# 01_MCU.net
KiCad netlist of a schematic drawn in Altium Designer
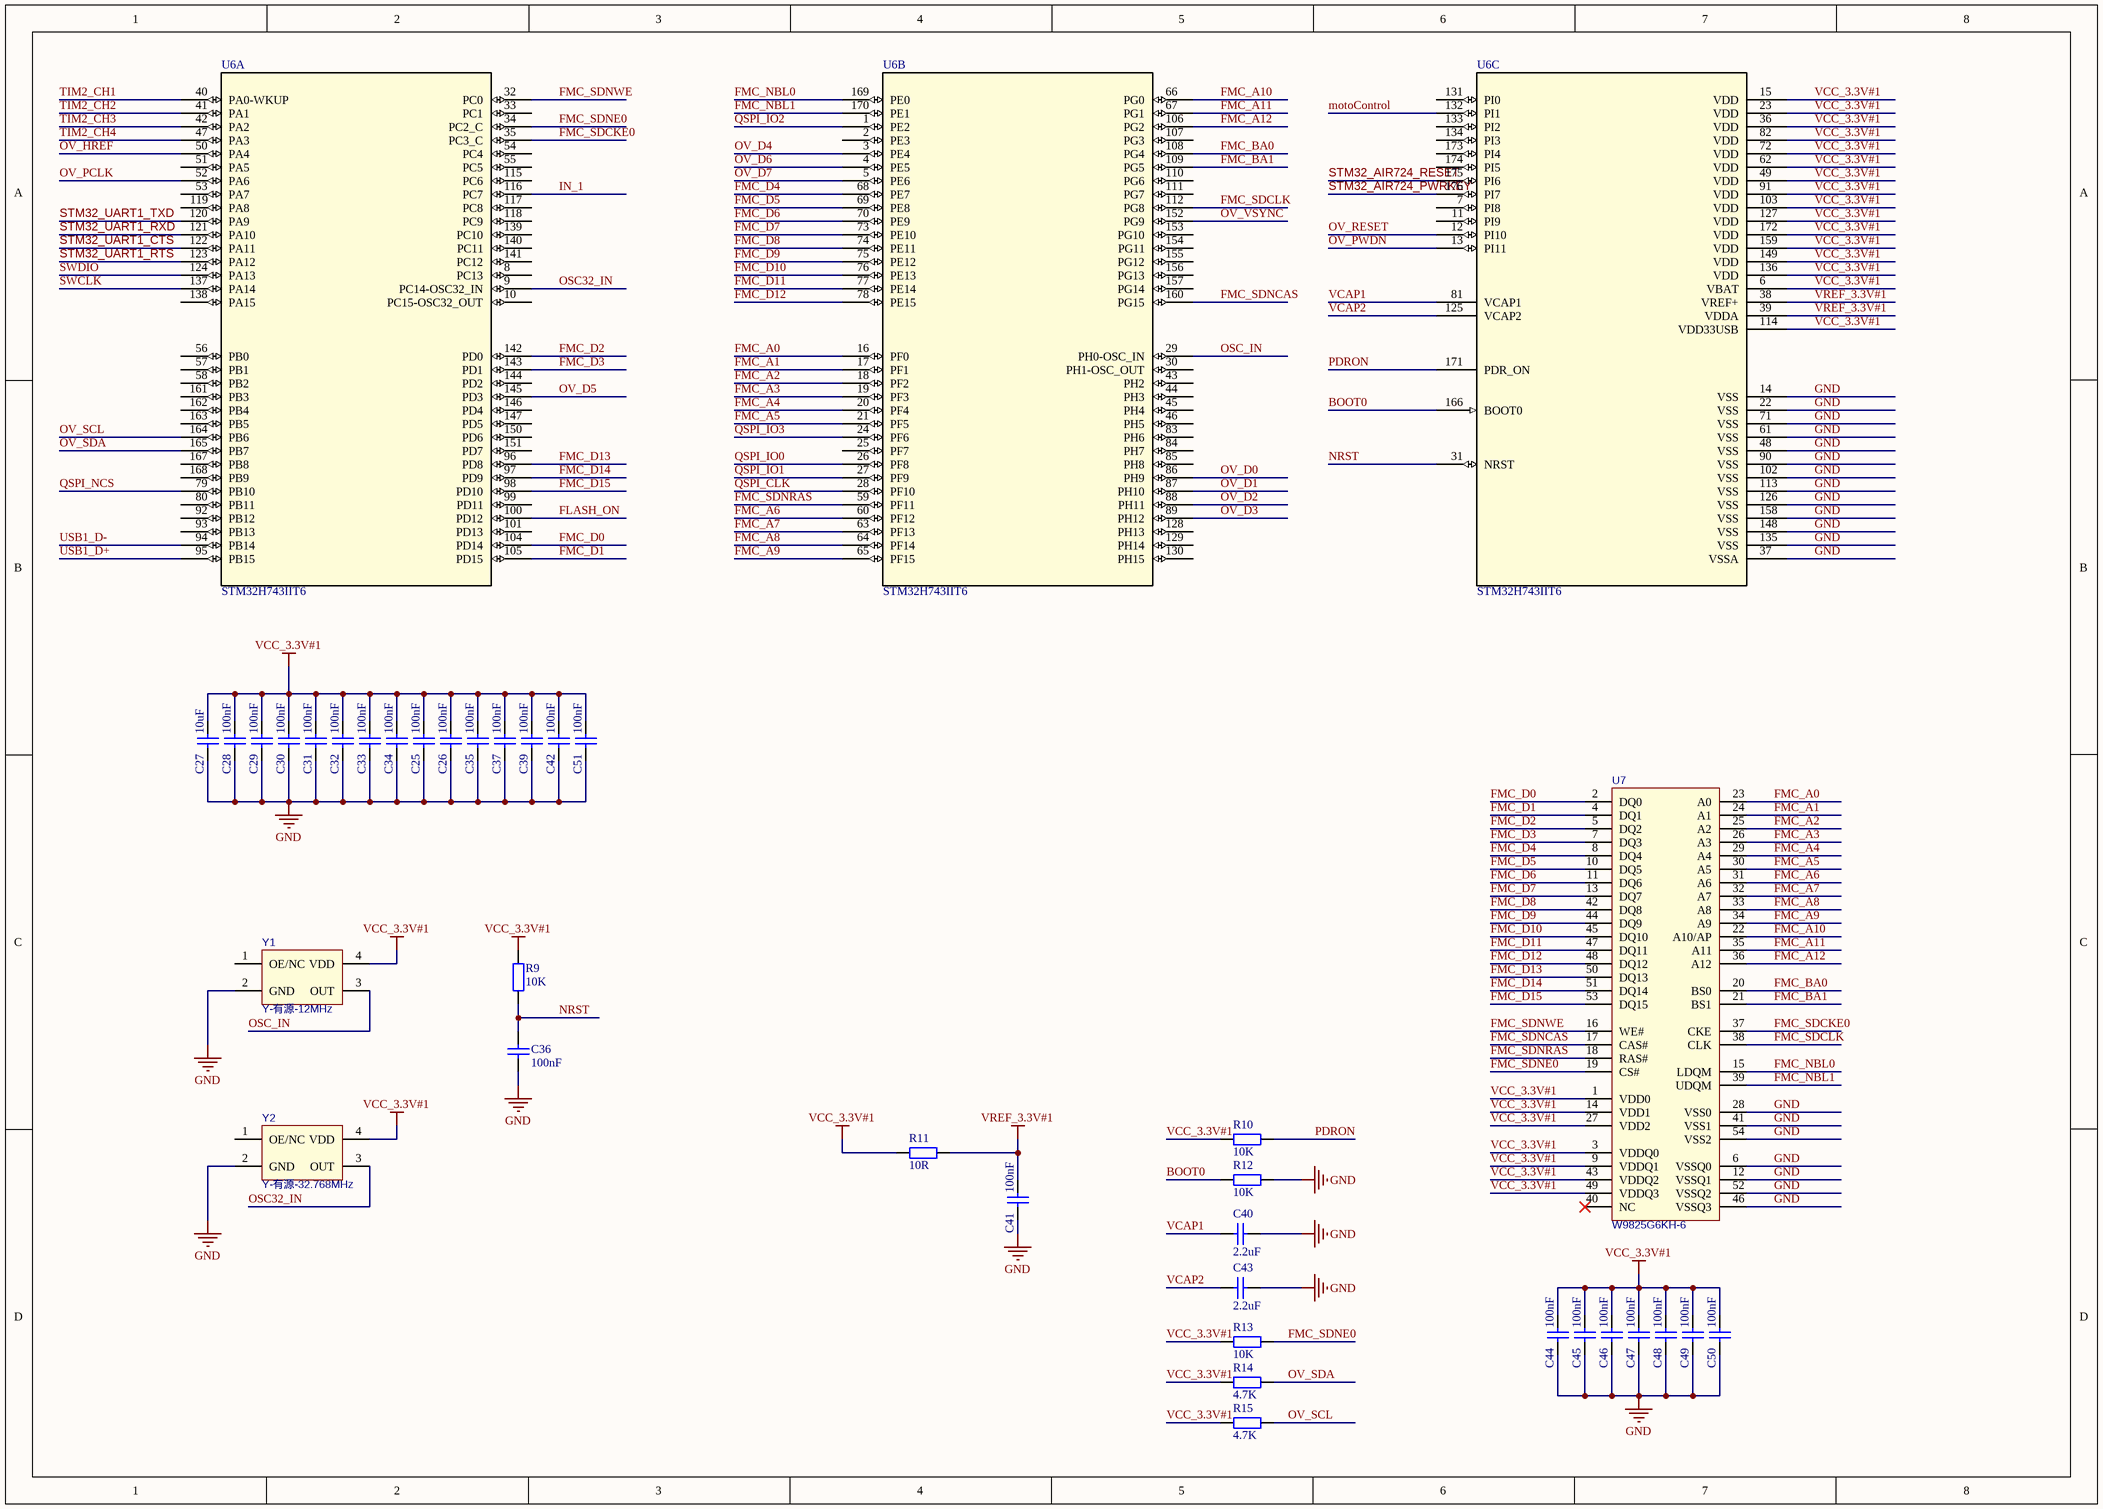
[diagram p0: 01_MCU.SchDoc]

(export (version "E")
  (design (tool "Eeschema 10.0.6"))
  (components
    (comp (ref "C25")
      (value "100nF")
      (footprint "0603-C")
      (description "贴片电容")
      (libsource (lib "封装库") (part "C"))
    )
    (comp (ref "C26")
      (value "100nF")
      (footprint "0603-C")
      (description "贴片电容")
      (libsource (lib "封装库") (part "C"))
    )
    (comp (ref "C27")
      (value "10uF")
      (footprint "0603-C")
      (description "贴片电容")
      (libsource (lib "封装库") (part "C"))
    )
    (comp (ref "C28")
      (value "100nF")
      (footprint "0603-C")
      (description "贴片电容")
      (libsource (lib "封装库") (part "C"))
    )
    (comp (ref "C29")
      (value "100nF")
      (footprint "0603-C")
      (description "贴片电容")
      (libsource (lib "封装库") (part "C"))
    )
    (comp (ref "C30")
      (value "100nF")
      (footprint "0603-C")
      (description "贴片电容")
      (libsource (lib "封装库") (part "C"))
    )
    (comp (ref "C31")
      (value "100nF")
      (footprint "0603-C")
      (description "贴片电容")
      (libsource (lib "封装库") (part "C"))
    )
    (comp (ref "C32")
      (value "100nF")
      (footprint "0603-C")
      (description "贴片电容")
      (libsource (lib "封装库") (part "C"))
    )
    (comp (ref "C33")
      (value "100nF")
      (footprint "0603-C")
      (description "贴片电容")
      (libsource (lib "封装库") (part "C"))
    )
    (comp (ref "C34")
      (value "100nF")
      (footprint "0603-C")
      (description "贴片电容")
      (libsource (lib "封装库") (part "C"))
    )
    (comp (ref "C35")
      (value "100nF")
      (footprint "0603-C")
      (description "贴片电容")
      (libsource (lib "封装库") (part "C"))
    )
    (comp (ref "C36")
      (value "100nF")
      (footprint "0603-C")
      (description "贴片电容")
      (libsource (lib "封装库") (part "C"))
    )
    (comp (ref "C37")
      (value "100nF")
      (footprint "0603-C")
      (description "贴片电容")
      (libsource (lib "封装库") (part "C"))
    )
    (comp (ref "C39")
      (value "100nF")
      (footprint "0603-C")
      (description "贴片电容")
      (libsource (lib "封装库") (part "C"))
    )
    (comp (ref "C40")
      (value "2.2uF")
      (footprint "0603-C")
      (description "贴片电容")
      (libsource (lib "封装库") (part "C"))
    )
    (comp (ref "C41")
      (value "100nF")
      (footprint "0603-C")
      (description "贴片电容")
      (libsource (lib "封装库") (part "C"))
    )
    (comp (ref "C42")
      (value "100nF")
      (footprint "0603-C")
      (description "贴片电容")
      (libsource (lib "封装库") (part "C"))
    )
    (comp (ref "C43")
      (value "2.2uF")
      (footprint "0603-C")
      (description "贴片电容")
      (libsource (lib "封装库") (part "C"))
    )
    (comp (ref "C44")
      (value "100nF")
      (footprint "0603-C")
      (description "贴片电容")
      (libsource (lib "封装库") (part "C"))
    )
    (comp (ref "C45")
      (value "100nF")
      (footprint "0603-C")
      (description "贴片电容")
      (libsource (lib "封装库") (part "C"))
    )
    (comp (ref "C46")
      (value "100nF")
      (footprint "0603-C")
      (description "贴片电容")
      (libsource (lib "封装库") (part "C"))
    )
    (comp (ref "C47")
      (value "100nF")
      (footprint "0603-C")
      (description "贴片电容")
      (libsource (lib "封装库") (part "C"))
    )
    (comp (ref "C48")
      (value "100nF")
      (footprint "0603-C")
      (description "贴片电容")
      (libsource (lib "封装库") (part "C"))
    )
    (comp (ref "C49")
      (value "100nF")
      (footprint "0603-C")
      (description "贴片电容")
      (libsource (lib "封装库") (part "C"))
    )
    (comp (ref "C50")
      (value "100nF")
      (footprint "0603-C")
      (description "贴片电容")
      (libsource (lib "封装库") (part "C"))
    )
    (comp (ref "C51")
      (value "100nF")
      (footprint "0603-C")
      (description "贴片电容")
      (libsource (lib "封装库") (part "C"))
    )
    (comp (ref "R9")
      (value "10K")
      (footprint "0603-R")
      (description "贴片电阻")
      (libsource (lib "封装库") (part "R"))
    )
    (comp (ref "R10")
      (value "10K")
      (footprint "0603-R")
      (description "贴片电阻")
      (libsource (lib "封装库") (part "R"))
    )
    (comp (ref "R11")
      (value "10R")
      (footprint "0603-R")
      (description "贴片电阻")
      (libsource (lib "封装库") (part "R"))
    )
    (comp (ref "R12")
      (value "10K")
      (footprint "0603-R")
      (description "贴片电阻")
      (libsource (lib "封装库") (part "R"))
    )
    (comp (ref "R13")
      (value "10K")
      (footprint "0603-R")
      (description "贴片电阻")
      (libsource (lib "封装库") (part "R"))
    )
    (comp (ref "R14")
      (value "4.7K")
      (footprint "0603-R")
      (description "贴片电阻")
      (libsource (lib "封装库") (part "R"))
    )
    (comp (ref "R15")
      (value "4.7K")
      (footprint "0603-R")
      (description "贴片电阻")
      (libsource (lib "封装库") (part "R"))
    )
    (comp (ref "U6")
      (value "STM32H743IIT6")
      (footprint "LQFP176-24x24mm")
      (description "No Description Available")
      (fields (field (name "COPYRIGHT") "Copyright (C) 2023 Ultra Librarian. All rights reserved."))
      (libsource (lib "封装库") (part "STM32H743IIT6"))
    )
    (comp (ref "U7")
      (value "W9825G6KH-6")
      (footprint "W9825G6KH-6")
      (fields (field (name "BOM_SUPPLIER PART") "C62246"))
      (libsource (lib "封装库") (part "W9825G6KH-6"))
    )
    (comp (ref "Y1")
      (value "Y-有源-12MHz")
      (footprint "3225")
      (description "有源晶振")
      (fields
        (field (name "BOM_SUPPLIER PART") "C2831396")
        (field (name "BOM_MANUFACTURER PART") "OT322540MJBA4SL")
        (field (name "CONTRIBUTOR") "LCSC")
      )
      (libsource (lib "封装库") (part "Y-有源"))
    )
    (comp (ref "Y2")
      (value "Y-有源-32.768MHz")
      (footprint "3225")
      (description "有源晶振")
      (fields
        (field (name "BOM_SUPPLIER PART") "C2831396")
        (field (name "BOM_MANUFACTURER PART") "OT322540MJBA4SL")
        (field (name "CONTRIBUTOR") "LCSC")
      )
      (libsource (lib "封装库") (part "Y-有源"))
    )
  )
  (nets
    (net (code "1") (name "/BOOT0") (class "Default")
      (node (ref "R12") (pin "2") (pinfunction "2_2") (pintype "passive"))
      (node (ref "U6") (pin "166") (pinfunction "BOOT0_166") (pintype "input"))
    )
    (net (code "2") (name "/FLASH_ON") (class "Default")
      (node (ref "U6") (pin "100") (pinfunction "PD12_100") (pintype "bidirectional"))
    )
    (net (code "3") (name "/FMC_A0") (class "Default")
      (node (ref "U6") (pin "16") (pinfunction "PF0_16") (pintype "bidirectional"))
      (node (ref "U7") (pin "23") (pinfunction "A0_23") (pintype "passive"))
    )
    (net (code "4") (name "/FMC_A1") (class "Default")
      (node (ref "U6") (pin "17") (pinfunction "PF1_17") (pintype "bidirectional"))
      (node (ref "U7") (pin "24") (pinfunction "A1_24") (pintype "passive"))
    )
    (net (code "5") (name "/FMC_A2") (class "Default")
      (node (ref "U6") (pin "18") (pinfunction "PF2_18") (pintype "bidirectional"))
      (node (ref "U7") (pin "25") (pinfunction "A2_25") (pintype "passive"))
    )
    (net (code "6") (name "/FMC_A3") (class "Default")
      (node (ref "U6") (pin "19") (pinfunction "PF3_19") (pintype "bidirectional"))
      (node (ref "U7") (pin "26") (pinfunction "A3_26") (pintype "passive"))
    )
    (net (code "7") (name "/FMC_A4") (class "Default")
      (node (ref "U6") (pin "20") (pinfunction "PF4_20") (pintype "bidirectional"))
      (node (ref "U7") (pin "29") (pinfunction "A4_29") (pintype "passive"))
    )
    (net (code "8") (name "/FMC_A5") (class "Default")
      (node (ref "U6") (pin "21") (pinfunction "PF5_21") (pintype "bidirectional"))
      (node (ref "U7") (pin "30") (pinfunction "A5_30") (pintype "passive"))
    )
    (net (code "9") (name "/FMC_A6") (class "Default")
      (node (ref "U6") (pin "60") (pinfunction "PF12_60") (pintype "bidirectional"))
      (node (ref "U7") (pin "31") (pinfunction "A6_31") (pintype "passive"))
    )
    (net (code "10") (name "/FMC_A7") (class "Default")
      (node (ref "U6") (pin "63") (pinfunction "PF13_63") (pintype "bidirectional"))
      (node (ref "U7") (pin "32") (pinfunction "A7_32") (pintype "passive"))
    )
    (net (code "11") (name "/FMC_A8") (class "Default")
      (node (ref "U6") (pin "64") (pinfunction "PF14_64") (pintype "bidirectional"))
      (node (ref "U7") (pin "33") (pinfunction "A8_33") (pintype "passive"))
    )
    (net (code "12") (name "/FMC_A9") (class "Default")
      (node (ref "U6") (pin "65") (pinfunction "PF15_65") (pintype "bidirectional"))
      (node (ref "U7") (pin "34") (pinfunction "A9_34") (pintype "passive"))
    )
    (net (code "13") (name "/FMC_A10") (class "Default")
      (node (ref "U6") (pin "66") (pinfunction "PG0_66") (pintype "bidirectional"))
      (node (ref "U7") (pin "22") (pinfunction "A10/AP_22") (pintype "passive"))
    )
    (net (code "14") (name "/FMC_A11") (class "Default")
      (node (ref "U6") (pin "67") (pinfunction "PG1_67") (pintype "bidirectional"))
      (node (ref "U7") (pin "35") (pinfunction "A11_35") (pintype "passive"))
    )
    (net (code "15") (name "/FMC_A12") (class "Default")
      (node (ref "U6") (pin "106") (pinfunction "PG2_106") (pintype "bidirectional"))
      (node (ref "U7") (pin "36") (pinfunction "A12_36") (pintype "passive"))
    )
    (net (code "16") (name "/FMC_BA0") (class "Default")
      (node (ref "U6") (pin "108") (pinfunction "PG4_108") (pintype "bidirectional"))
      (node (ref "U7") (pin "20") (pinfunction "BS0_20") (pintype "passive"))
    )
    (net (code "17") (name "/FMC_BA1") (class "Default")
      (node (ref "U6") (pin "109") (pinfunction "PG5_109") (pintype "bidirectional"))
      (node (ref "U7") (pin "21") (pinfunction "BS1_21") (pintype "passive"))
    )
    (net (code "18") (name "/FMC_D0") (class "Default")
      (node (ref "U6") (pin "104") (pinfunction "PD14_104") (pintype "bidirectional"))
      (node (ref "U7") (pin "2") (pinfunction "DQ0_2") (pintype "passive"))
    )
    (net (code "19") (name "/FMC_D1") (class "Default")
      (node (ref "U6") (pin "105") (pinfunction "PD15_105") (pintype "bidirectional"))
      (node (ref "U7") (pin "4") (pinfunction "DQ1_4") (pintype "passive"))
    )
    (net (code "20") (name "/FMC_D2") (class "Default")
      (node (ref "U6") (pin "142") (pinfunction "PD0_142") (pintype "bidirectional"))
      (node (ref "U7") (pin "5") (pinfunction "DQ2_5") (pintype "passive"))
    )
    (net (code "21") (name "/FMC_D3") (class "Default")
      (node (ref "U6") (pin "143") (pinfunction "PD1_143") (pintype "bidirectional"))
      (node (ref "U7") (pin "7") (pinfunction "DQ3_7") (pintype "passive"))
    )
    (net (code "22") (name "/FMC_D4") (class "Default")
      (node (ref "U6") (pin "68") (pinfunction "PE7_68") (pintype "bidirectional"))
      (node (ref "U7") (pin "8") (pinfunction "DQ4_8") (pintype "passive"))
    )
    (net (code "23") (name "/FMC_D5") (class "Default")
      (node (ref "U6") (pin "69") (pinfunction "PE8_69") (pintype "bidirectional"))
      (node (ref "U7") (pin "10") (pinfunction "DQ5_10") (pintype "passive"))
    )
    (net (code "24") (name "/FMC_D6") (class "Default")
      (node (ref "U6") (pin "70") (pinfunction "PE9_70") (pintype "bidirectional"))
      (node (ref "U7") (pin "11") (pinfunction "DQ6_11") (pintype "passive"))
    )
    (net (code "25") (name "/FMC_D7") (class "Default")
      (node (ref "U6") (pin "73") (pinfunction "PE10_73") (pintype "bidirectional"))
      (node (ref "U7") (pin "13") (pinfunction "DQ7_13") (pintype "passive"))
    )
    (net (code "26") (name "/FMC_D8") (class "Default")
      (node (ref "U6") (pin "74") (pinfunction "PE11_74") (pintype "bidirectional"))
      (node (ref "U7") (pin "42") (pinfunction "DQ8_42") (pintype "passive"))
    )
    (net (code "27") (name "/FMC_D9") (class "Default")
      (node (ref "U6") (pin "75") (pinfunction "PE12_75") (pintype "bidirectional"))
      (node (ref "U7") (pin "44") (pinfunction "DQ9_44") (pintype "passive"))
    )
    (net (code "28") (name "/FMC_D10") (class "Default")
      (node (ref "U6") (pin "76") (pinfunction "PE13_76") (pintype "bidirectional"))
      (node (ref "U7") (pin "45") (pinfunction "DQ10_45") (pintype "passive"))
    )
    (net (code "29") (name "/FMC_D11") (class "Default")
      (node (ref "U6") (pin "77") (pinfunction "PE14_77") (pintype "bidirectional"))
      (node (ref "U7") (pin "47") (pinfunction "DQ11_47") (pintype "passive"))
    )
    (net (code "30") (name "/FMC_D12") (class "Default")
      (node (ref "U6") (pin "78") (pinfunction "PE15_78") (pintype "bidirectional"))
      (node (ref "U7") (pin "48") (pinfunction "DQ12_48") (pintype "passive"))
    )
    (net (code "31") (name "/FMC_D13") (class "Default")
      (node (ref "U6") (pin "96") (pinfunction "PD8_96") (pintype "bidirectional"))
      (node (ref "U7") (pin "50") (pinfunction "DQ13_50") (pintype "passive"))
    )
    (net (code "32") (name "/FMC_D14") (class "Default")
      (node (ref "U6") (pin "97") (pinfunction "PD9_97") (pintype "bidirectional"))
      (node (ref "U7") (pin "51") (pinfunction "DQ14_51") (pintype "passive"))
    )
    (net (code "33") (name "/FMC_D15") (class "Default")
      (node (ref "U6") (pin "98") (pinfunction "PD10_98") (pintype "bidirectional"))
      (node (ref "U7") (pin "53") (pinfunction "DQ15_53") (pintype "passive"))
    )
    (net (code "34") (name "/FMC_NBL0") (class "Default")
      (node (ref "U6") (pin "169") (pinfunction "PE0_169") (pintype "bidirectional"))
      (node (ref "U7") (pin "15") (pinfunction "LDQM_15") (pintype "passive"))
    )
    (net (code "35") (name "/FMC_NBL1") (class "Default")
      (node (ref "U6") (pin "170") (pinfunction "PE1_170") (pintype "bidirectional"))
      (node (ref "U7") (pin "39") (pinfunction "UDQM_39") (pintype "passive"))
    )
    (net (code "36") (name "/FMC_SDCKE0") (class "Default")
      (node (ref "U6") (pin "35") (pinfunction "PC3_C_35") (pintype "bidirectional"))
      (node (ref "U7") (pin "37") (pinfunction "CKE_37") (pintype "passive"))
    )
    (net (code "37") (name "/FMC_SDCLK") (class "Default")
      (node (ref "U6") (pin "112") (pinfunction "PG8_112") (pintype "bidirectional"))
      (node (ref "U7") (pin "38") (pinfunction "CLK_38") (pintype "passive"))
    )
    (net (code "38") (name "/FMC_SDNCAS") (class "Default")
      (node (ref "U6") (pin "160") (pinfunction "PG15_160") (pintype "bidirectional"))
      (node (ref "U7") (pin "17") (pinfunction "CAS#_17") (pintype "passive"))
    )
    (net (code "39") (name "/FMC_SDNE0") (class "Default")
      (node (ref "R13") (pin "1") (pinfunction "1_1") (pintype "passive"))
      (node (ref "U6") (pin "34") (pinfunction "PC2_C_34") (pintype "bidirectional"))
      (node (ref "U7") (pin "19") (pinfunction "CS#_19") (pintype "passive"))
    )
    (net (code "40") (name "/FMC_SDNRAS") (class "Default")
      (node (ref "U6") (pin "59") (pinfunction "PF11_59") (pintype "bidirectional"))
      (node (ref "U7") (pin "18") (pinfunction "RAS#_18") (pintype "passive"))
    )
    (net (code "41") (name "/FMC_SDNWE") (class "Default")
      (node (ref "U6") (pin "32") (pinfunction "PC0_32") (pintype "bidirectional"))
      (node (ref "U7") (pin "16") (pinfunction "WE#_16") (pintype "passive"))
    )
    (net (code "42") (name "/IN_1") (class "Default")
      (node (ref "U6") (pin "116") (pinfunction "PC7_116") (pintype "bidirectional"))
    )
    (net (code "43") (name "/NRST") (class "Default")
      (node (ref "C36") (pin "2") (pinfunction "2_2") (pintype "passive"))
      (node (ref "R9") (pin "1") (pinfunction "1_1") (pintype "passive"))
      (node (ref "U6") (pin "31") (pinfunction "NRST_31") (pintype "bidirectional"))
    )
    (net (code "44") (name "/OSC32_IN") (class "Default")
      (node (ref "U6") (pin "9") (pinfunction "PC14-OSC32_IN_9") (pintype "bidirectional"))
      (node (ref "Y2") (pin "3") (pinfunction "OUT_3") (pintype "passive"))
    )
    (net (code "45") (name "/OSC_IN") (class "Default")
      (node (ref "U6") (pin "29") (pinfunction "PH0-OSC_IN_29") (pintype "bidirectional"))
      (node (ref "Y1") (pin "3") (pinfunction "OUT_3") (pintype "passive"))
    )
    (net (code "46") (name "/OV_D0") (class "Default")
      (node (ref "U6") (pin "86") (pinfunction "PH9_86") (pintype "bidirectional"))
    )
    (net (code "47") (name "/OV_D1") (class "Default")
      (node (ref "U6") (pin "87") (pinfunction "PH10_87") (pintype "bidirectional"))
    )
    (net (code "48") (name "/OV_D2") (class "Default")
      (node (ref "U6") (pin "88") (pinfunction "PH11_88") (pintype "bidirectional"))
    )
    (net (code "49") (name "/OV_D3") (class "Default")
      (node (ref "U6") (pin "89") (pinfunction "PH12_89") (pintype "bidirectional"))
    )
    (net (code "50") (name "/OV_D4") (class "Default")
      (node (ref "U6") (pin "3") (pinfunction "PE4_3") (pintype "bidirectional"))
    )
    (net (code "51") (name "/OV_D5") (class "Default")
      (node (ref "U6") (pin "145") (pinfunction "PD3_145") (pintype "bidirectional"))
    )
    (net (code "52") (name "/OV_D6") (class "Default")
      (node (ref "U6") (pin "4") (pinfunction "PE5_4") (pintype "bidirectional"))
    )
    (net (code "53") (name "/OV_D7") (class "Default")
      (node (ref "U6") (pin "5") (pinfunction "PE6_5") (pintype "bidirectional"))
    )
    (net (code "54") (name "/OV_HREF") (class "Default")
      (node (ref "U6") (pin "50") (pinfunction "PA4_50") (pintype "bidirectional"))
    )
    (net (code "55") (name "/OV_PCLK") (class "Default")
      (node (ref "U6") (pin "52") (pinfunction "PA6_52") (pintype "bidirectional"))
    )
    (net (code "56") (name "/OV_PWDN") (class "Default")
      (node (ref "U6") (pin "13") (pinfunction "PI11_13") (pintype "bidirectional"))
    )
    (net (code "57") (name "/OV_RESET") (class "Default")
      (node (ref "U6") (pin "12") (pinfunction "PI10_12") (pintype "bidirectional"))
    )
    (net (code "58") (name "/OV_SCL") (class "Default")
      (node (ref "R15") (pin "1") (pinfunction "1_1") (pintype "passive"))
      (node (ref "U6") (pin "164") (pinfunction "PB6_164") (pintype "bidirectional"))
    )
    (net (code "59") (name "/OV_SDA") (class "Default")
      (node (ref "R14") (pin "1") (pinfunction "1_1") (pintype "passive"))
      (node (ref "U6") (pin "165") (pinfunction "PB7_165") (pintype "bidirectional"))
    )
    (net (code "60") (name "/OV_VSYNC") (class "Default")
      (node (ref "U6") (pin "152") (pinfunction "PG9_152") (pintype "bidirectional"))
    )
    (net (code "61") (name "/PDRON") (class "Default")
      (node (ref "R10") (pin "1") (pinfunction "1_1") (pintype "passive"))
      (node (ref "U6") (pin "171") (pinfunction "PDR_ON_171") (pintype "passive"))
    )
    (net (code "62") (name "/QSPI_CLK") (class "Default")
      (node (ref "U6") (pin "28") (pinfunction "PF10_28") (pintype "bidirectional"))
    )
    (net (code "63") (name "/QSPI_IO0") (class "Default")
      (node (ref "U6") (pin "26") (pinfunction "PF8_26") (pintype "bidirectional"))
    )
    (net (code "64") (name "/QSPI_IO1") (class "Default")
      (node (ref "U6") (pin "27") (pinfunction "PF9_27") (pintype "bidirectional"))
    )
    (net (code "65") (name "/QSPI_IO2") (class "Default")
      (node (ref "U6") (pin "1") (pinfunction "PE2_1") (pintype "bidirectional"))
    )
    (net (code "66") (name "/QSPI_IO3") (class "Default")
      (node (ref "U6") (pin "24") (pinfunction "PF6_24") (pintype "bidirectional"))
    )
    (net (code "67") (name "/QSPI_NCS") (class "Default")
      (node (ref "U6") (pin "79") (pinfunction "PB10_79") (pintype "bidirectional"))
    )
    (net (code "68") (name "/STM32_AIR724_PWRKEY") (class "Default")
      (node (ref "U6") (pin "176") (pinfunction "PI7_176") (pintype "bidirectional"))
    )
    (net (code "69") (name "/STM32_AIR724_RESET") (class "Default")
      (node (ref "U6") (pin "175") (pinfunction "PI6_175") (pintype "bidirectional"))
    )
    (net (code "70") (name "/STM32_UART1_CTS") (class "Default")
      (node (ref "U6") (pin "122") (pinfunction "PA11_122") (pintype "bidirectional"))
    )
    (net (code "71") (name "/STM32_UART1_RTS") (class "Default")
      (node (ref "U6") (pin "123") (pinfunction "PA12_123") (pintype "bidirectional"))
    )
    (net (code "72") (name "/STM32_UART1_RXD") (class "Default")
      (node (ref "U6") (pin "121") (pinfunction "PA10_121") (pintype "bidirectional"))
    )
    (net (code "73") (name "/STM32_UART1_TXD") (class "Default")
      (node (ref "U6") (pin "120") (pinfunction "PA9_120") (pintype "bidirectional"))
    )
    (net (code "74") (name "/SWCLK") (class "Default")
      (node (ref "U6") (pin "137") (pinfunction "PA14_137") (pintype "bidirectional"))
    )
    (net (code "75") (name "/SWDIO") (class "Default")
      (node (ref "U6") (pin "124") (pinfunction "PA13_124") (pintype "bidirectional"))
    )
    (net (code "76") (name "/TIM2_CH1") (class "Default")
      (node (ref "U6") (pin "40") (pinfunction "PA0-WKUP_40") (pintype "bidirectional"))
    )
    (net (code "77") (name "/TIM2_CH2") (class "Default")
      (node (ref "U6") (pin "41") (pinfunction "PA1_41") (pintype "bidirectional"))
    )
    (net (code "78") (name "/TIM2_CH3") (class "Default")
      (node (ref "U6") (pin "42") (pinfunction "PA2_42") (pintype "bidirectional"))
    )
    (net (code "79") (name "/TIM2_CH4") (class "Default")
      (node (ref "U6") (pin "47") (pinfunction "PA3_47") (pintype "bidirectional"))
    )
    (net (code "80") (name "/USB1_D+") (class "Default")
      (node (ref "U6") (pin "95") (pinfunction "PB15_95") (pintype "bidirectional"))
    )
    (net (code "81") (name "/USB1_D-") (class "Default")
      (node (ref "U6") (pin "94") (pinfunction "PB14_94") (pintype "bidirectional"))
    )
    (net (code "82") (name "/VCAP1") (class "Default")
      (node (ref "C40") (pin "1") (pinfunction "1_1") (pintype "passive"))
      (node (ref "U6") (pin "81") (pinfunction "VCAP1_81") (pintype "power_in"))
    )
    (net (code "83") (name "/VCAP2") (class "Default")
      (node (ref "C43") (pin "1") (pinfunction "1_1") (pintype "passive"))
      (node (ref "U6") (pin "125") (pinfunction "VCAP2_125") (pintype "power_in"))
    )
    (net (code "84") (name "/motoControl") (class "Default")
      (node (ref "U6") (pin "132") (pinfunction "PI1_132") (pintype "bidirectional"))
    )
    (net (code "85") (name "GND") (class "Default")
      (node (ref "C25") (pin "1") (pinfunction "1_1") (pintype "passive"))
      (node (ref "C26") (pin "1") (pinfunction "1_1") (pintype "passive"))
      (node (ref "C27") (pin "1") (pinfunction "1_1") (pintype "passive"))
      (node (ref "C28") (pin "1") (pinfunction "1_1") (pintype "passive"))
      (node (ref "C29") (pin "1") (pinfunction "1_1") (pintype "passive"))
      (node (ref "C30") (pin "1") (pinfunction "1_1") (pintype "passive"))
      (node (ref "C31") (pin "1") (pinfunction "1_1") (pintype "passive"))
      (node (ref "C32") (pin "1") (pinfunction "1_1") (pintype "passive"))
      (node (ref "C33") (pin "1") (pinfunction "1_1") (pintype "passive"))
      (node (ref "C34") (pin "1") (pinfunction "1_1") (pintype "passive"))
      (node (ref "C35") (pin "1") (pinfunction "1_1") (pintype "passive"))
      (node (ref "C36") (pin "1") (pinfunction "1_1") (pintype "passive"))
      (node (ref "C37") (pin "1") (pinfunction "1_1") (pintype "passive"))
      (node (ref "C39") (pin "1") (pinfunction "1_1") (pintype "passive"))
      (node (ref "C40") (pin "2") (pinfunction "2_2") (pintype "passive"))
      (node (ref "C41") (pin "1") (pinfunction "1_1") (pintype "passive"))
      (node (ref "C42") (pin "1") (pinfunction "1_1") (pintype "passive"))
      (node (ref "C43") (pin "2") (pinfunction "2_2") (pintype "passive"))
      (node (ref "C44") (pin "1") (pinfunction "1_1") (pintype "passive"))
      (node (ref "C45") (pin "1") (pinfunction "1_1") (pintype "passive"))
      (node (ref "C46") (pin "1") (pinfunction "1_1") (pintype "passive"))
      (node (ref "C47") (pin "1") (pinfunction "1_1") (pintype "passive"))
      (node (ref "C48") (pin "1") (pinfunction "1_1") (pintype "passive"))
      (node (ref "C49") (pin "1") (pinfunction "1_1") (pintype "passive"))
      (node (ref "C50") (pin "1") (pinfunction "1_1") (pintype "passive"))
      (node (ref "C51") (pin "1") (pinfunction "1_1") (pintype "passive"))
      (node (ref "R12") (pin "1") (pinfunction "1_1") (pintype "passive"))
      (node (ref "U6") (pin "102") (pinfunction "VSS_102") (pintype "power_in"))
      (node (ref "U6") (pin "113") (pinfunction "VSS_113") (pintype "power_in"))
      (node (ref "U6") (pin "126") (pinfunction "VSS_126") (pintype "power_in"))
      (node (ref "U6") (pin "135") (pinfunction "VSS_135") (pintype "power_in"))
      (node (ref "U6") (pin "14") (pinfunction "VSS_14") (pintype "power_in"))
      (node (ref "U6") (pin "148") (pinfunction "VSS_148") (pintype "power_in"))
      (node (ref "U6") (pin "158") (pinfunction "VSS_158") (pintype "power_in"))
      (node (ref "U6") (pin "22") (pinfunction "VSS_22") (pintype "power_in"))
      (node (ref "U6") (pin "37") (pinfunction "VSSA_37") (pintype "power_in"))
      (node (ref "U6") (pin "48") (pinfunction "VSS_48") (pintype "power_in"))
      (node (ref "U6") (pin "61") (pinfunction "VSS_61") (pintype "power_in"))
      (node (ref "U6") (pin "71") (pinfunction "VSS_71") (pintype "power_in"))
      (node (ref "U6") (pin "90") (pinfunction "VSS_90") (pintype "power_in"))
      (node (ref "U7") (pin "12") (pinfunction "VSSQ1_12") (pintype "passive"))
      (node (ref "U7") (pin "28") (pinfunction "VSS0_28") (pintype "passive"))
      (node (ref "U7") (pin "41") (pinfunction "VSS1_41") (pintype "passive"))
      (node (ref "U7") (pin "46") (pinfunction "VSSQ3_46") (pintype "passive"))
      (node (ref "U7") (pin "52") (pinfunction "VSSQ2_52") (pintype "passive"))
      (node (ref "U7") (pin "54") (pinfunction "VSS2_54") (pintype "passive"))
      (node (ref "U7") (pin "6") (pinfunction "VSSQ0_6") (pintype "passive"))
      (node (ref "Y1") (pin "2") (pinfunction "GND_2") (pintype "passive"))
      (node (ref "Y2") (pin "2") (pinfunction "GND_2") (pintype "passive"))
    )
    (net (code "86") (name "VCC_3.3V#1") (class "Default")
      (node (ref "C25") (pin "2") (pinfunction "2_2") (pintype "passive"))
      (node (ref "C26") (pin "2") (pinfunction "2_2") (pintype "passive"))
      (node (ref "C27") (pin "2") (pinfunction "2_2") (pintype "passive"))
      (node (ref "C28") (pin "2") (pinfunction "2_2") (pintype "passive"))
      (node (ref "C29") (pin "2") (pinfunction "2_2") (pintype "passive"))
      (node (ref "C30") (pin "2") (pinfunction "2_2") (pintype "passive"))
      (node (ref "C31") (pin "2") (pinfunction "2_2") (pintype "passive"))
      (node (ref "C32") (pin "2") (pinfunction "2_2") (pintype "passive"))
      (node (ref "C33") (pin "2") (pinfunction "2_2") (pintype "passive"))
      (node (ref "C34") (pin "2") (pinfunction "2_2") (pintype "passive"))
      (node (ref "C35") (pin "2") (pinfunction "2_2") (pintype "passive"))
      (node (ref "C37") (pin "2") (pinfunction "2_2") (pintype "passive"))
      (node (ref "C39") (pin "2") (pinfunction "2_2") (pintype "passive"))
      (node (ref "C42") (pin "2") (pinfunction "2_2") (pintype "passive"))
      (node (ref "C44") (pin "2") (pinfunction "2_2") (pintype "passive"))
      (node (ref "C45") (pin "2") (pinfunction "2_2") (pintype "passive"))
      (node (ref "C46") (pin "2") (pinfunction "2_2") (pintype "passive"))
      (node (ref "C47") (pin "2") (pinfunction "2_2") (pintype "passive"))
      (node (ref "C48") (pin "2") (pinfunction "2_2") (pintype "passive"))
      (node (ref "C49") (pin "2") (pinfunction "2_2") (pintype "passive"))
      (node (ref "C50") (pin "2") (pinfunction "2_2") (pintype "passive"))
      (node (ref "C51") (pin "2") (pinfunction "2_2") (pintype "passive"))
      (node (ref "R10") (pin "2") (pinfunction "2_2") (pintype "passive"))
      (node (ref "R11") (pin "2") (pinfunction "2_2") (pintype "passive"))
      (node (ref "R13") (pin "2") (pinfunction "2_2") (pintype "passive"))
      (node (ref "R14") (pin "2") (pinfunction "2_2") (pintype "passive"))
      (node (ref "R15") (pin "2") (pinfunction "2_2") (pintype "passive"))
      (node (ref "R9") (pin "2") (pinfunction "2_2") (pintype "passive"))
      (node (ref "U6") (pin "103") (pinfunction "VDD_103") (pintype "power_in"))
      (node (ref "U6") (pin "114") (pinfunction "VDD33USB_114") (pintype "power_in"))
      (node (ref "U6") (pin "127") (pinfunction "VDD_127") (pintype "power_in"))
      (node (ref "U6") (pin "136") (pinfunction "VDD_136") (pintype "power_in"))
      (node (ref "U6") (pin "149") (pinfunction "VDD_149") (pintype "power_in"))
      (node (ref "U6") (pin "15") (pinfunction "VDD_15") (pintype "power_in"))
      (node (ref "U6") (pin "159") (pinfunction "VDD_159") (pintype "power_in"))
      (node (ref "U6") (pin "172") (pinfunction "VDD_172") (pintype "power_in"))
      (node (ref "U6") (pin "23") (pinfunction "VDD_23") (pintype "power_in"))
      (node (ref "U6") (pin "36") (pinfunction "VDD_36") (pintype "power_in"))
      (node (ref "U6") (pin "49") (pinfunction "VDD_49") (pintype "power_in"))
      (node (ref "U6") (pin "6") (pinfunction "VBAT_6") (pintype "power_in"))
      (node (ref "U6") (pin "62") (pinfunction "VDD_62") (pintype "power_in"))
      (node (ref "U6") (pin "72") (pinfunction "VDD_72") (pintype "power_in"))
      (node (ref "U6") (pin "82") (pinfunction "VDD_82") (pintype "power_in"))
      (node (ref "U6") (pin "91") (pinfunction "VDD_91") (pintype "power_in"))
      (node (ref "U7") (pin "1") (pinfunction "VDD0_1") (pintype "passive"))
      (node (ref "U7") (pin "14") (pinfunction "VDD1_14") (pintype "passive"))
      (node (ref "U7") (pin "27") (pinfunction "VDD2_27") (pintype "passive"))
      (node (ref "U7") (pin "3") (pinfunction "VDDQ0_3") (pintype "passive"))
      (node (ref "U7") (pin "43") (pinfunction "VDDQ2_43") (pintype "passive"))
      (node (ref "U7") (pin "49") (pinfunction "VDDQ3_49") (pintype "passive"))
      (node (ref "U7") (pin "9") (pinfunction "VDDQ1_9") (pintype "passive"))
      (node (ref "Y1") (pin "4") (pinfunction "VDD_4") (pintype "passive"))
      (node (ref "Y2") (pin "4") (pinfunction "VDD_4") (pintype "passive"))
    )
    (net (code "87") (name "VREF_3.3V#1") (class "Default")
      (node (ref "C41") (pin "2") (pinfunction "2_2") (pintype "passive"))
      (node (ref "R11") (pin "1") (pinfunction "1_1") (pintype "passive"))
      (node (ref "U6") (pin "38") (pinfunction "VREF+_38") (pintype "power_in"))
      (node (ref "U6") (pin "39") (pinfunction "VDDA_39") (pintype "power_in"))
    )
    (net (code "88") (name "unconnected-(U6A-PA5-Pad51)") (class "Default")
      (node (ref "U6") (pin "51") (pinfunction "PA5_51") (pintype "bidirectional"))
    )
    (net (code "89") (name "unconnected-(U6A-PA7-Pad53)") (class "Default")
      (node (ref "U6") (pin "53") (pinfunction "PA7_53") (pintype "bidirectional"))
    )
    (net (code "90") (name "unconnected-(U6A-PA8-Pad119)") (class "Default")
      (node (ref "U6") (pin "119") (pinfunction "PA8_119") (pintype "bidirectional"))
    )
    (net (code "91") (name "unconnected-(U6A-PA15-Pad138)") (class "Default")
      (node (ref "U6") (pin "138") (pinfunction "PA15_138") (pintype "bidirectional"))
    )
    (net (code "92") (name "unconnected-(U6A-PB0-Pad56)") (class "Default")
      (node (ref "U6") (pin "56") (pinfunction "PB0_56") (pintype "bidirectional"))
    )
    (net (code "93") (name "unconnected-(U6A-PB1-Pad57)") (class "Default")
      (node (ref "U6") (pin "57") (pinfunction "PB1_57") (pintype "bidirectional"))
    )
    (net (code "94") (name "unconnected-(U6A-PB2-Pad58)") (class "Default")
      (node (ref "U6") (pin "58") (pinfunction "PB2_58") (pintype "bidirectional"))
    )
    (net (code "95") (name "unconnected-(U6A-PB3-Pad161)") (class "Default")
      (node (ref "U6") (pin "161") (pinfunction "PB3_161") (pintype "bidirectional"))
    )
    (net (code "96") (name "unconnected-(U6A-PB4-Pad162)") (class "Default")
      (node (ref "U6") (pin "162") (pinfunction "PB4_162") (pintype "bidirectional"))
    )
    (net (code "97") (name "unconnected-(U6A-PB5-Pad163)") (class "Default")
      (node (ref "U6") (pin "163") (pinfunction "PB5_163") (pintype "bidirectional"))
    )
    (net (code "98") (name "unconnected-(U6A-PB8-Pad167)") (class "Default")
      (node (ref "U6") (pin "167") (pinfunction "PB8_167") (pintype "bidirectional"))
    )
    (net (code "99") (name "unconnected-(U6A-PB9-Pad168)") (class "Default")
      (node (ref "U6") (pin "168") (pinfunction "PB9_168") (pintype "bidirectional"))
    )
    (net (code "100") (name "unconnected-(U6A-PB11-Pad80)") (class "Default")
      (node (ref "U6") (pin "80") (pinfunction "PB11_80") (pintype "bidirectional"))
    )
    (net (code "101") (name "unconnected-(U6A-PB12-Pad92)") (class "Default")
      (node (ref "U6") (pin "92") (pinfunction "PB12_92") (pintype "bidirectional"))
    )
    (net (code "102") (name "unconnected-(U6A-PB13-Pad93)") (class "Default")
      (node (ref "U6") (pin "93") (pinfunction "PB13_93") (pintype "bidirectional"))
    )
    (net (code "103") (name "unconnected-(U6A-PC1-Pad33)") (class "Default")
      (node (ref "U6") (pin "33") (pinfunction "PC1_33") (pintype "bidirectional"))
    )
    (net (code "104") (name "unconnected-(U6A-PC4-Pad54)") (class "Default")
      (node (ref "U6") (pin "54") (pinfunction "PC4_54") (pintype "bidirectional"))
    )
    (net (code "105") (name "unconnected-(U6A-PC5-Pad55)") (class "Default")
      (node (ref "U6") (pin "55") (pinfunction "PC5_55") (pintype "bidirectional"))
    )
    (net (code "106") (name "unconnected-(U6A-PC6-Pad115)") (class "Default")
      (node (ref "U6") (pin "115") (pinfunction "PC6_115") (pintype "bidirectional"))
    )
    (net (code "107") (name "unconnected-(U6A-PC8-Pad117)") (class "Default")
      (node (ref "U6") (pin "117") (pinfunction "PC8_117") (pintype "bidirectional"))
    )
    (net (code "108") (name "unconnected-(U6A-PC9-Pad118)") (class "Default")
      (node (ref "U6") (pin "118") (pinfunction "PC9_118") (pintype "bidirectional"))
    )
    (net (code "109") (name "unconnected-(U6A-PC10-Pad139)") (class "Default")
      (node (ref "U6") (pin "139") (pinfunction "PC10_139") (pintype "bidirectional"))
    )
    (net (code "110") (name "unconnected-(U6A-PC11-Pad140)") (class "Default")
      (node (ref "U6") (pin "140") (pinfunction "PC11_140") (pintype "bidirectional"))
    )
    (net (code "111") (name "unconnected-(U6A-PC12-Pad141)") (class "Default")
      (node (ref "U6") (pin "141") (pinfunction "PC12_141") (pintype "bidirectional"))
    )
    (net (code "112") (name "unconnected-(U6A-PC13-Pad8)") (class "Default")
      (node (ref "U6") (pin "8") (pinfunction "PC13_8") (pintype "bidirectional"))
    )
    (net (code "113") (name "unconnected-(U6A-PC15-OSC32_OUT-Pad10)") (class "Default")
      (node (ref "U6") (pin "10") (pinfunction "PC15-OSC32_OUT_10") (pintype "bidirectional"))
    )
    (net (code "114") (name "unconnected-(U6A-PD2-Pad144)") (class "Default")
      (node (ref "U6") (pin "144") (pinfunction "PD2_144") (pintype "bidirectional"))
    )
    (net (code "115") (name "unconnected-(U6A-PD4-Pad146)") (class "Default")
      (node (ref "U6") (pin "146") (pinfunction "PD4_146") (pintype "bidirectional"))
    )
    (net (code "116") (name "unconnected-(U6A-PD5-Pad147)") (class "Default")
      (node (ref "U6") (pin "147") (pinfunction "PD5_147") (pintype "bidirectional"))
    )
    (net (code "117") (name "unconnected-(U6A-PD6-Pad150)") (class "Default")
      (node (ref "U6") (pin "150") (pinfunction "PD6_150") (pintype "bidirectional"))
    )
    (net (code "118") (name "unconnected-(U6A-PD7-Pad151)") (class "Default")
      (node (ref "U6") (pin "151") (pinfunction "PD7_151") (pintype "bidirectional"))
    )
    (net (code "119") (name "unconnected-(U6A-PD11-Pad99)") (class "Default")
      (node (ref "U6") (pin "99") (pinfunction "PD11_99") (pintype "bidirectional"))
    )
    (net (code "120") (name "unconnected-(U6A-PD13-Pad101)") (class "Default")
      (node (ref "U6") (pin "101") (pinfunction "PD13_101") (pintype "bidirectional"))
    )
    (net (code "121") (name "unconnected-(U6B-PE3-Pad2)") (class "Default")
      (node (ref "U6") (pin "2") (pinfunction "PE3_2") (pintype "bidirectional"))
    )
    (net (code "122") (name "unconnected-(U6B-PF7-Pad25)") (class "Default")
      (node (ref "U6") (pin "25") (pinfunction "PF7_25") (pintype "bidirectional"))
    )
    (net (code "123") (name "unconnected-(U6B-PG3-Pad107)") (class "Default")
      (node (ref "U6") (pin "107") (pinfunction "PG3_107") (pintype "bidirectional"))
    )
    (net (code "124") (name "unconnected-(U6B-PG6-Pad110)") (class "Default")
      (node (ref "U6") (pin "110") (pinfunction "PG6_110") (pintype "bidirectional"))
    )
    (net (code "125") (name "unconnected-(U6B-PG7-Pad111)") (class "Default")
      (node (ref "U6") (pin "111") (pinfunction "PG7_111") (pintype "bidirectional"))
    )
    (net (code "126") (name "unconnected-(U6B-PG10-Pad153)") (class "Default")
      (node (ref "U6") (pin "153") (pinfunction "PG10_153") (pintype "bidirectional"))
    )
    (net (code "127") (name "unconnected-(U6B-PG11-Pad154)") (class "Default")
      (node (ref "U6") (pin "154") (pinfunction "PG11_154") (pintype "bidirectional"))
    )
    (net (code "128") (name "unconnected-(U6B-PG12-Pad155)") (class "Default")
      (node (ref "U6") (pin "155") (pinfunction "PG12_155") (pintype "bidirectional"))
    )
    (net (code "129") (name "unconnected-(U6B-PG13-Pad156)") (class "Default")
      (node (ref "U6") (pin "156") (pinfunction "PG13_156") (pintype "bidirectional"))
    )
    (net (code "130") (name "unconnected-(U6B-PG14-Pad157)") (class "Default")
      (node (ref "U6") (pin "157") (pinfunction "PG14_157") (pintype "bidirectional"))
    )
    (net (code "131") (name "unconnected-(U6B-PH1-OSC_OUT-Pad30)") (class "Default")
      (node (ref "U6") (pin "30") (pinfunction "PH1-OSC_OUT_30") (pintype "bidirectional"))
    )
    (net (code "132") (name "unconnected-(U6B-PH2-Pad43)") (class "Default")
      (node (ref "U6") (pin "43") (pinfunction "PH2_43") (pintype "bidirectional"))
    )
    (net (code "133") (name "unconnected-(U6B-PH3-Pad44)") (class "Default")
      (node (ref "U6") (pin "44") (pinfunction "PH3_44") (pintype "bidirectional"))
    )
    (net (code "134") (name "unconnected-(U6B-PH4-Pad45)") (class "Default")
      (node (ref "U6") (pin "45") (pinfunction "PH4_45") (pintype "bidirectional"))
    )
    (net (code "135") (name "unconnected-(U6B-PH5-Pad46)") (class "Default")
      (node (ref "U6") (pin "46") (pinfunction "PH5_46") (pintype "bidirectional"))
    )
    (net (code "136") (name "unconnected-(U6B-PH6-Pad83)") (class "Default")
      (node (ref "U6") (pin "83") (pinfunction "PH6_83") (pintype "bidirectional"))
    )
    (net (code "137") (name "unconnected-(U6B-PH7-Pad84)") (class "Default")
      (node (ref "U6") (pin "84") (pinfunction "PH7_84") (pintype "bidirectional"))
    )
    (net (code "138") (name "unconnected-(U6B-PH8-Pad85)") (class "Default")
      (node (ref "U6") (pin "85") (pinfunction "PH8_85") (pintype "bidirectional"))
    )
    (net (code "139") (name "unconnected-(U6B-PH13-Pad128)") (class "Default")
      (node (ref "U6") (pin "128") (pinfunction "PH13_128") (pintype "bidirectional"))
    )
    (net (code "140") (name "unconnected-(U6B-PH14-Pad129)") (class "Default")
      (node (ref "U6") (pin "129") (pinfunction "PH14_129") (pintype "bidirectional"))
    )
    (net (code "141") (name "unconnected-(U6B-PH15-Pad130)") (class "Default")
      (node (ref "U6") (pin "130") (pinfunction "PH15_130") (pintype "bidirectional"))
    )
    (net (code "142") (name "unconnected-(U6C-PI0-Pad131)") (class "Default")
      (node (ref "U6") (pin "131") (pinfunction "PI0_131") (pintype "bidirectional"))
    )
    (net (code "143") (name "unconnected-(U6C-PI2-Pad133)") (class "Default")
      (node (ref "U6") (pin "133") (pinfunction "PI2_133") (pintype "bidirectional"))
    )
    (net (code "144") (name "unconnected-(U6C-PI3-Pad134)") (class "Default")
      (node (ref "U6") (pin "134") (pinfunction "PI3_134") (pintype "bidirectional"))
    )
    (net (code "145") (name "unconnected-(U6C-PI4-Pad173)") (class "Default")
      (node (ref "U6") (pin "173") (pinfunction "PI4_173") (pintype "bidirectional"))
    )
    (net (code "146") (name "unconnected-(U6C-PI5-Pad174)") (class "Default")
      (node (ref "U6") (pin "174") (pinfunction "PI5_174") (pintype "bidirectional"))
    )
    (net (code "147") (name "unconnected-(U6C-PI8-Pad7)") (class "Default")
      (node (ref "U6") (pin "7") (pinfunction "PI8_7") (pintype "bidirectional"))
    )
    (net (code "148") (name "unconnected-(U6C-PI9-Pad11)") (class "Default")
      (node (ref "U6") (pin "11") (pinfunction "PI9_11") (pintype "bidirectional"))
    )
    (net (code "149") (name "unconnected-(U7-NC-Pad40)") (class "Default")
      (node (ref "U7") (pin "40") (pinfunction "NC_40") (pintype "passive+no_connect"))
    )
    (net (code "150") (name "unconnected-(Y1-OE{slash}NC-Pad1)") (class "Default")
      (node (ref "Y1") (pin "1") (pinfunction "OE/NC_1") (pintype "passive"))
    )
    (net (code "151") (name "unconnected-(Y2-OE{slash}NC-Pad1)") (class "Default")
      (node (ref "Y2") (pin "1") (pinfunction "OE/NC_1") (pintype "passive"))
    )
  )
)
